# relay_block2.net
KiCad netlist of a schematic drawn in EAGLE
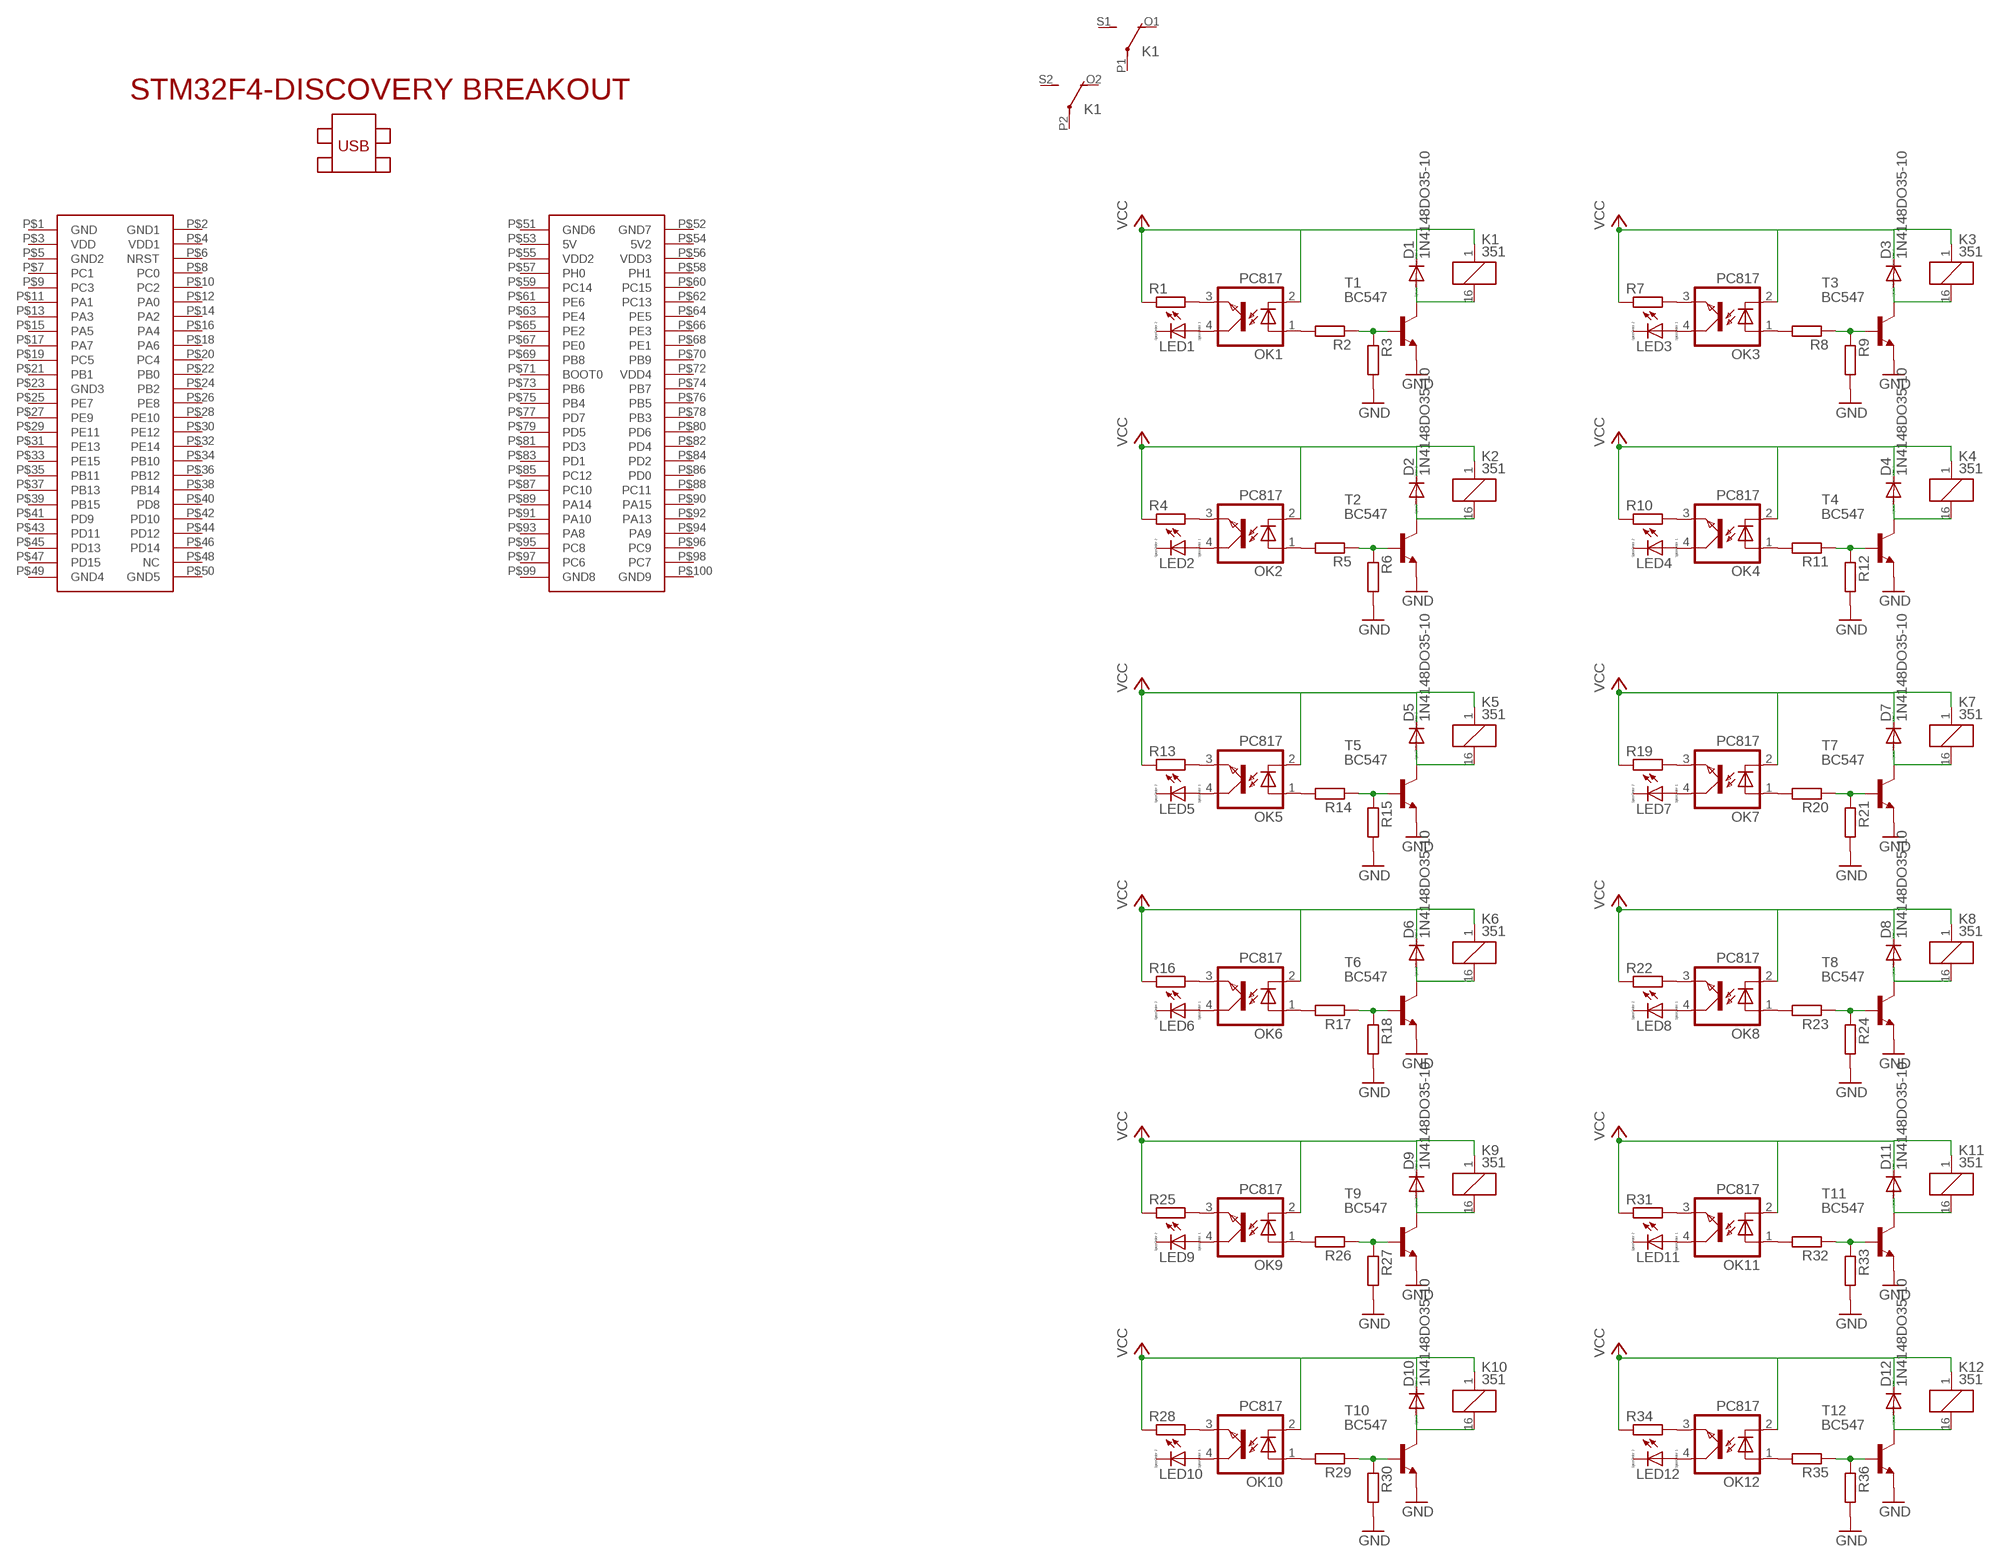
[diagram p0: schematic, sheet 1]

(export (version "E")
  (design (tool "Eeschema 10.0.6"))
  (components
    (comp (ref "D1")
      (value "1N4148DO35-10")
      (footprint "eagle-import:DO35-10")
      (libsource (lib "eagle-import") (part "1N4148DO35-10"))
    )
    (comp (ref "D2")
      (value "1N4148DO35-10")
      (footprint "eagle-import:DO35-10")
      (libsource (lib "eagle-import") (part "1N4148DO35-10"))
    )
    (comp (ref "D3")
      (value "1N4148DO35-10")
      (footprint "eagle-import:DO35-10")
      (libsource (lib "eagle-import") (part "1N4148DO35-10"))
    )
    (comp (ref "D4")
      (value "1N4148DO35-10")
      (footprint "eagle-import:DO35-10")
      (libsource (lib "eagle-import") (part "1N4148DO35-10"))
    )
    (comp (ref "D5")
      (value "1N4148DO35-10")
      (footprint "eagle-import:DO35-10")
      (libsource (lib "eagle-import") (part "1N4148DO35-10"))
    )
    (comp (ref "D6")
      (value "1N4148DO35-10")
      (footprint "eagle-import:DO35-10")
      (libsource (lib "eagle-import") (part "1N4148DO35-10"))
    )
    (comp (ref "D7")
      (value "1N4148DO35-10")
      (footprint "eagle-import:DO35-10")
      (libsource (lib "eagle-import") (part "1N4148DO35-10"))
    )
    (comp (ref "D8")
      (value "1N4148DO35-10")
      (footprint "eagle-import:DO35-10")
      (libsource (lib "eagle-import") (part "1N4148DO35-10"))
    )
    (comp (ref "D9")
      (value "1N4148DO35-10")
      (footprint "eagle-import:DO35-10")
      (libsource (lib "eagle-import") (part "1N4148DO35-10"))
    )
    (comp (ref "D10")
      (value "1N4148DO35-10")
      (footprint "eagle-import:DO35-10")
      (libsource (lib "eagle-import") (part "1N4148DO35-10"))
    )
    (comp (ref "D11")
      (value "1N4148DO35-10")
      (footprint "eagle-import:DO35-10")
      (libsource (lib "eagle-import") (part "1N4148DO35-10"))
    )
    (comp (ref "D12")
      (value "1N4148DO35-10")
      (footprint "eagle-import:DO35-10")
      (libsource (lib "eagle-import") (part "1N4148DO35-10"))
    )
    (comp (ref "K1")
      (value "351")
      (footprint "eagle-import:351")
      (libsource (lib "eagle-import") (part "351"))
    )
    (comp (ref "K2")
      (value "351")
      (footprint "eagle-import:351")
      (libsource (lib "eagle-import") (part "351"))
    )
    (comp (ref "K3")
      (value "351")
      (footprint "eagle-import:351")
      (libsource (lib "eagle-import") (part "351"))
    )
    (comp (ref "K4")
      (value "351")
      (footprint "eagle-import:351")
      (libsource (lib "eagle-import") (part "351"))
    )
    (comp (ref "K5")
      (value "351")
      (footprint "eagle-import:351")
      (libsource (lib "eagle-import") (part "351"))
    )
    (comp (ref "K6")
      (value "351")
      (footprint "eagle-import:351")
      (libsource (lib "eagle-import") (part "351"))
    )
    (comp (ref "K7")
      (value "351")
      (footprint "eagle-import:351")
      (libsource (lib "eagle-import") (part "351"))
    )
    (comp (ref "K8")
      (value "351")
      (footprint "eagle-import:351")
      (libsource (lib "eagle-import") (part "351"))
    )
    (comp (ref "K9")
      (value "351")
      (footprint "eagle-import:351")
      (libsource (lib "eagle-import") (part "351"))
    )
    (comp (ref "K10")
      (value "351")
      (footprint "eagle-import:351")
      (libsource (lib "eagle-import") (part "351"))
    )
    (comp (ref "K11")
      (value "351")
      (footprint "eagle-import:351")
      (libsource (lib "eagle-import") (part "351"))
    )
    (comp (ref "K12")
      (value "351")
      (footprint "eagle-import:351")
      (libsource (lib "eagle-import") (part "351"))
    )
    (comp (ref "LED1")
      (value "LED_ELD260")
      (footprint "eagle-import:LED_LD260")
      (libsource (lib "eagle-import") (part "LED_ELD260"))
    )
    (comp (ref "LED2")
      (value "LED_ELD260")
      (footprint "eagle-import:LED_LD260")
      (libsource (lib "eagle-import") (part "LED_ELD260"))
    )
    (comp (ref "LED3")
      (value "LED_ELD260")
      (footprint "eagle-import:LED_LD260")
      (libsource (lib "eagle-import") (part "LED_ELD260"))
    )
    (comp (ref "LED4")
      (value "LED_ELD260")
      (footprint "eagle-import:LED_LD260")
      (libsource (lib "eagle-import") (part "LED_ELD260"))
    )
    (comp (ref "LED5")
      (value "LED_ELD260")
      (footprint "eagle-import:LED_LD260")
      (libsource (lib "eagle-import") (part "LED_ELD260"))
    )
    (comp (ref "LED6")
      (value "LED_ELD260")
      (footprint "eagle-import:LED_LD260")
      (libsource (lib "eagle-import") (part "LED_ELD260"))
    )
    (comp (ref "LED7")
      (value "LED_ELD260")
      (footprint "eagle-import:LED_LD260")
      (libsource (lib "eagle-import") (part "LED_ELD260"))
    )
    (comp (ref "LED8")
      (value "LED_ELD260")
      (footprint "eagle-import:LED_LD260")
      (libsource (lib "eagle-import") (part "LED_ELD260"))
    )
    (comp (ref "LED9")
      (value "LED_ELD260")
      (footprint "eagle-import:LED_LD260")
      (libsource (lib "eagle-import") (part "LED_ELD260"))
    )
    (comp (ref "LED10")
      (value "LED_ELD260")
      (footprint "eagle-import:LED_LD260")
      (libsource (lib "eagle-import") (part "LED_ELD260"))
    )
    (comp (ref "LED11")
      (value "LED_ELD260")
      (footprint "eagle-import:LED_LD260")
      (libsource (lib "eagle-import") (part "LED_ELD260"))
    )
    (comp (ref "LED12")
      (value "LED_ELD260")
      (footprint "eagle-import:LED_LD260")
      (libsource (lib "eagle-import") (part "LED_ELD260"))
    )
    (comp (ref "OK1")
      (value "PC817")
      (footprint "eagle-import:DIL04")
      (fields (field (name "MPN") "PC817X4J000F"))
      (libsource (lib "eagle-import") (part "PC817"))
    )
    (comp (ref "OK2")
      (value "PC817")
      (footprint "eagle-import:DIL04")
      (fields (field (name "MPN") "PC817X4J000F"))
      (libsource (lib "eagle-import") (part "PC817"))
    )
    (comp (ref "OK3")
      (value "PC817")
      (footprint "eagle-import:DIL04")
      (fields (field (name "MPN") "PC817X4J000F"))
      (libsource (lib "eagle-import") (part "PC817"))
    )
    (comp (ref "OK4")
      (value "PC817")
      (footprint "eagle-import:DIL04")
      (fields (field (name "MPN") "PC817X4J000F"))
      (libsource (lib "eagle-import") (part "PC817"))
    )
    (comp (ref "OK5")
      (value "PC817")
      (footprint "eagle-import:DIL04")
      (fields (field (name "MPN") "PC817X4J000F"))
      (libsource (lib "eagle-import") (part "PC817"))
    )
    (comp (ref "OK6")
      (value "PC817")
      (footprint "eagle-import:DIL04")
      (fields (field (name "MPN") "PC817X4J000F"))
      (libsource (lib "eagle-import") (part "PC817"))
    )
    (comp (ref "OK7")
      (value "PC817")
      (footprint "eagle-import:DIL04")
      (fields (field (name "MPN") "PC817X4J000F"))
      (libsource (lib "eagle-import") (part "PC817"))
    )
    (comp (ref "OK8")
      (value "PC817")
      (footprint "eagle-import:DIL04")
      (fields (field (name "MPN") "PC817X4J000F"))
      (libsource (lib "eagle-import") (part "PC817"))
    )
    (comp (ref "OK9")
      (value "PC817")
      (footprint "eagle-import:DIL04")
      (fields (field (name "MPN") "PC817X4J000F"))
      (libsource (lib "eagle-import") (part "PC817"))
    )
    (comp (ref "OK10")
      (value "PC817")
      (footprint "eagle-import:DIL04")
      (fields (field (name "MPN") "PC817X4J000F"))
      (libsource (lib "eagle-import") (part "PC817"))
    )
    (comp (ref "OK11")
      (value "PC817")
      (footprint "eagle-import:DIL04")
      (fields (field (name "MPN") "PC817X4J000F"))
      (libsource (lib "eagle-import") (part "PC817"))
    )
    (comp (ref "OK12")
      (value "PC817")
      (footprint "eagle-import:DIL04")
      (fields (field (name "MPN") "PC817X4J000F"))
      (libsource (lib "eagle-import") (part "PC817"))
    )
    (comp (ref "R1")
      (value "R-EU_M1206")
      (footprint "eagle-import:M1206")
      (libsource (lib "eagle-import") (part "R-EU_M1206"))
    )
    (comp (ref "R2")
      (value "R-EU_M1206")
      (footprint "eagle-import:M1206")
      (libsource (lib "eagle-import") (part "R-EU_M1206"))
    )
    (comp (ref "R3")
      (value "R-EU_M1206")
      (footprint "eagle-import:M1206")
      (libsource (lib "eagle-import") (part "R-EU_M1206"))
    )
    (comp (ref "R4")
      (value "R-EU_M1206")
      (footprint "eagle-import:M1206")
      (libsource (lib "eagle-import") (part "R-EU_M1206"))
    )
    (comp (ref "R5")
      (value "R-EU_M1206")
      (footprint "eagle-import:M1206")
      (libsource (lib "eagle-import") (part "R-EU_M1206"))
    )
    (comp (ref "R6")
      (value "R-EU_M1206")
      (footprint "eagle-import:M1206")
      (libsource (lib "eagle-import") (part "R-EU_M1206"))
    )
    (comp (ref "R7")
      (value "R-EU_M1206")
      (footprint "eagle-import:M1206")
      (libsource (lib "eagle-import") (part "R-EU_M1206"))
    )
    (comp (ref "R8")
      (value "R-EU_M1206")
      (footprint "eagle-import:M1206")
      (libsource (lib "eagle-import") (part "R-EU_M1206"))
    )
    (comp (ref "R9")
      (value "R-EU_M1206")
      (footprint "eagle-import:M1206")
      (libsource (lib "eagle-import") (part "R-EU_M1206"))
    )
    (comp (ref "R10")
      (value "R-EU_M1206")
      (footprint "eagle-import:M1206")
      (libsource (lib "eagle-import") (part "R-EU_M1206"))
    )
    (comp (ref "R11")
      (value "R-EU_M1206")
      (footprint "eagle-import:M1206")
      (libsource (lib "eagle-import") (part "R-EU_M1206"))
    )
    (comp (ref "R12")
      (value "R-EU_M1206")
      (footprint "eagle-import:M1206")
      (libsource (lib "eagle-import") (part "R-EU_M1206"))
    )
    (comp (ref "R13")
      (value "R-EU_M1206")
      (footprint "eagle-import:M1206")
      (libsource (lib "eagle-import") (part "R-EU_M1206"))
    )
    (comp (ref "R14")
      (value "R-EU_M1206")
      (footprint "eagle-import:M1206")
      (libsource (lib "eagle-import") (part "R-EU_M1206"))
    )
    (comp (ref "R15")
      (value "R-EU_M1206")
      (footprint "eagle-import:M1206")
      (libsource (lib "eagle-import") (part "R-EU_M1206"))
    )
    (comp (ref "R16")
      (value "R-EU_M1206")
      (footprint "eagle-import:M1206")
      (libsource (lib "eagle-import") (part "R-EU_M1206"))
    )
    (comp (ref "R17")
      (value "R-EU_M1206")
      (footprint "eagle-import:M1206")
      (libsource (lib "eagle-import") (part "R-EU_M1206"))
    )
    (comp (ref "R18")
      (value "R-EU_M1206")
      (footprint "eagle-import:M1206")
      (libsource (lib "eagle-import") (part "R-EU_M1206"))
    )
    (comp (ref "R19")
      (value "R-EU_M1206")
      (footprint "eagle-import:M1206")
      (libsource (lib "eagle-import") (part "R-EU_M1206"))
    )
    (comp (ref "R20")
      (value "R-EU_M1206")
      (footprint "eagle-import:M1206")
      (libsource (lib "eagle-import") (part "R-EU_M1206"))
    )
    (comp (ref "R21")
      (value "R-EU_M1206")
      (footprint "eagle-import:M1206")
      (libsource (lib "eagle-import") (part "R-EU_M1206"))
    )
    (comp (ref "R22")
      (value "R-EU_M1206")
      (footprint "eagle-import:M1206")
      (libsource (lib "eagle-import") (part "R-EU_M1206"))
    )
    (comp (ref "R23")
      (value "R-EU_M1206")
      (footprint "eagle-import:M1206")
      (libsource (lib "eagle-import") (part "R-EU_M1206"))
    )
    (comp (ref "R24")
      (value "R-EU_M1206")
      (footprint "eagle-import:M1206")
      (libsource (lib "eagle-import") (part "R-EU_M1206"))
    )
    (comp (ref "R25")
      (value "R-EU_M1206")
      (footprint "eagle-import:M1206")
      (libsource (lib "eagle-import") (part "R-EU_M1206"))
    )
    (comp (ref "R26")
      (value "R-EU_M1206")
      (footprint "eagle-import:M1206")
      (libsource (lib "eagle-import") (part "R-EU_M1206"))
    )
    (comp (ref "R27")
      (value "R-EU_M1206")
      (footprint "eagle-import:M1206")
      (libsource (lib "eagle-import") (part "R-EU_M1206"))
    )
    (comp (ref "R28")
      (value "R-EU_M1206")
      (footprint "eagle-import:M1206")
      (libsource (lib "eagle-import") (part "R-EU_M1206"))
    )
    (comp (ref "R29")
      (value "R-EU_M1206")
      (footprint "eagle-import:M1206")
      (libsource (lib "eagle-import") (part "R-EU_M1206"))
    )
    (comp (ref "R30")
      (value "R-EU_M1206")
      (footprint "eagle-import:M1206")
      (libsource (lib "eagle-import") (part "R-EU_M1206"))
    )
    (comp (ref "R31")
      (value "R-EU_M1206")
      (footprint "eagle-import:M1206")
      (libsource (lib "eagle-import") (part "R-EU_M1206"))
    )
    (comp (ref "R32")
      (value "R-EU_M1206")
      (footprint "eagle-import:M1206")
      (libsource (lib "eagle-import") (part "R-EU_M1206"))
    )
    (comp (ref "R33")
      (value "R-EU_M1206")
      (footprint "eagle-import:M1206")
      (libsource (lib "eagle-import") (part "R-EU_M1206"))
    )
    (comp (ref "R34")
      (value "R-EU_M1206")
      (footprint "eagle-import:M1206")
      (libsource (lib "eagle-import") (part "R-EU_M1206"))
    )
    (comp (ref "R35")
      (value "R-EU_M1206")
      (footprint "eagle-import:M1206")
      (libsource (lib "eagle-import") (part "R-EU_M1206"))
    )
    (comp (ref "R36")
      (value "R-EU_M1206")
      (footprint "eagle-import:M1206")
      (libsource (lib "eagle-import") (part "R-EU_M1206"))
    )
    (comp (ref "T1")
      (value "BC547")
      (footprint "eagle-import:TO92")
      (libsource (lib "eagle-import") (part "BC547"))
    )
    (comp (ref "T2")
      (value "BC547")
      (footprint "eagle-import:TO92")
      (libsource (lib "eagle-import") (part "BC547"))
    )
    (comp (ref "T3")
      (value "BC547")
      (footprint "eagle-import:TO92")
      (libsource (lib "eagle-import") (part "BC547"))
    )
    (comp (ref "T4")
      (value "BC547")
      (footprint "eagle-import:TO92")
      (libsource (lib "eagle-import") (part "BC547"))
    )
    (comp (ref "T5")
      (value "BC547")
      (footprint "eagle-import:TO92")
      (libsource (lib "eagle-import") (part "BC547"))
    )
    (comp (ref "T6")
      (value "BC547")
      (footprint "eagle-import:TO92")
      (libsource (lib "eagle-import") (part "BC547"))
    )
    (comp (ref "T7")
      (value "BC547")
      (footprint "eagle-import:TO92")
      (libsource (lib "eagle-import") (part "BC547"))
    )
    (comp (ref "T8")
      (value "BC547")
      (footprint "eagle-import:TO92")
      (libsource (lib "eagle-import") (part "BC547"))
    )
    (comp (ref "T9")
      (value "BC547")
      (footprint "eagle-import:TO92")
      (libsource (lib "eagle-import") (part "BC547"))
    )
    (comp (ref "T10")
      (value "BC547")
      (footprint "eagle-import:TO92")
      (libsource (lib "eagle-import") (part "BC547"))
    )
    (comp (ref "T11")
      (value "BC547")
      (footprint "eagle-import:TO92")
      (libsource (lib "eagle-import") (part "BC547"))
    )
    (comp (ref "T12")
      (value "BC547")
      (footprint "eagle-import:TO92")
      (libsource (lib "eagle-import") (part "BC547"))
    )
    (comp (ref "U$1")
      (value "STM32F4-DISCOVERY_STM32F4-DISCOVERY")
      (footprint "eagle-import:STM32F4-DISCOVERY_STM32F4-DISCOVERY")
      (libsource (lib "eagle-import") (part "STM32F4-DISCOVERY_STM32F4-DISCOVERY"))
    )
  )
  (nets
    (net (code "1") (name "GND") (class "Default")
      (node (ref "R12") (pin "2") (pinfunction "2_2") (pintype "passive"))
      (node (ref "R15") (pin "2") (pinfunction "2_2") (pintype "passive"))
      (node (ref "R18") (pin "2") (pinfunction "2_2") (pintype "passive"))
      (node (ref "R21") (pin "2") (pinfunction "2_2") (pintype "passive"))
      (node (ref "R24") (pin "2") (pinfunction "2_2") (pintype "passive"))
      (node (ref "R27") (pin "2") (pinfunction "2_2") (pintype "passive"))
      (node (ref "R3") (pin "2") (pinfunction "2_2") (pintype "passive"))
      (node (ref "R30") (pin "2") (pinfunction "2_2") (pintype "passive"))
      (node (ref "R33") (pin "2") (pinfunction "2_2") (pintype "passive"))
      (node (ref "R36") (pin "2") (pinfunction "2_2") (pintype "passive"))
      (node (ref "R6") (pin "2") (pinfunction "2_2") (pintype "passive"))
      (node (ref "R9") (pin "2") (pinfunction "2_2") (pintype "passive"))
      (node (ref "T1") (pin "1") (pinfunction "E_1") (pintype "passive"))
      (node (ref "T10") (pin "1") (pinfunction "E_1") (pintype "passive"))
      (node (ref "T11") (pin "1") (pinfunction "E_1") (pintype "passive"))
      (node (ref "T12") (pin "1") (pinfunction "E_1") (pintype "passive"))
      (node (ref "T2") (pin "1") (pinfunction "E_1") (pintype "passive"))
      (node (ref "T3") (pin "1") (pinfunction "E_1") (pintype "passive"))
      (node (ref "T4") (pin "1") (pinfunction "E_1") (pintype "passive"))
      (node (ref "T5") (pin "1") (pinfunction "E_1") (pintype "passive"))
      (node (ref "T6") (pin "1") (pinfunction "E_1") (pintype "passive"))
      (node (ref "T7") (pin "1") (pinfunction "E_1") (pintype "passive"))
      (node (ref "T8") (pin "1") (pinfunction "E_1") (pintype "passive"))
      (node (ref "T9") (pin "1") (pinfunction "E_1") (pintype "passive"))
    )
    (net (code "2") (name "Net-(K1A-2)") (class "Default")
      (node (ref "D1") (pin "A") (pinfunction "A_A") (pintype "passive"))
      (node (ref "K1") (pin "16") (pinfunction "2_16") (pintype "passive"))
      (node (ref "T1") (pin "3") (pinfunction "C_3") (pintype "passive"))
    )
    (net (code "3") (name "Net-(K2A-2)") (class "Default")
      (node (ref "D2") (pin "A") (pinfunction "A_A") (pintype "passive"))
      (node (ref "K2") (pin "16") (pinfunction "2_16") (pintype "passive"))
      (node (ref "T2") (pin "3") (pinfunction "C_3") (pintype "passive"))
    )
    (net (code "4") (name "Net-(K3A-2)") (class "Default")
      (node (ref "D3") (pin "A") (pinfunction "A_A") (pintype "passive"))
      (node (ref "K3") (pin "16") (pinfunction "2_16") (pintype "passive"))
      (node (ref "T3") (pin "3") (pinfunction "C_3") (pintype "passive"))
    )
    (net (code "5") (name "Net-(K4A-2)") (class "Default")
      (node (ref "D4") (pin "A") (pinfunction "A_A") (pintype "passive"))
      (node (ref "K4") (pin "16") (pinfunction "2_16") (pintype "passive"))
      (node (ref "T4") (pin "3") (pinfunction "C_3") (pintype "passive"))
    )
    (net (code "6") (name "Net-(K5A-2)") (class "Default")
      (node (ref "D5") (pin "A") (pinfunction "A_A") (pintype "passive"))
      (node (ref "K5") (pin "16") (pinfunction "2_16") (pintype "passive"))
      (node (ref "T5") (pin "3") (pinfunction "C_3") (pintype "passive"))
    )
    (net (code "7") (name "Net-(K6A-2)") (class "Default")
      (node (ref "D6") (pin "A") (pinfunction "A_A") (pintype "passive"))
      (node (ref "K6") (pin "16") (pinfunction "2_16") (pintype "passive"))
      (node (ref "T6") (pin "3") (pinfunction "C_3") (pintype "passive"))
    )
    (net (code "8") (name "Net-(K7A-2)") (class "Default")
      (node (ref "D7") (pin "A") (pinfunction "A_A") (pintype "passive"))
      (node (ref "K7") (pin "16") (pinfunction "2_16") (pintype "passive"))
      (node (ref "T7") (pin "3") (pinfunction "C_3") (pintype "passive"))
    )
    (net (code "9") (name "Net-(K8A-2)") (class "Default")
      (node (ref "D8") (pin "A") (pinfunction "A_A") (pintype "passive"))
      (node (ref "K8") (pin "16") (pinfunction "2_16") (pintype "passive"))
      (node (ref "T8") (pin "3") (pinfunction "C_3") (pintype "passive"))
    )
    (net (code "10") (name "Net-(K9A-2)") (class "Default")
      (node (ref "D9") (pin "A") (pinfunction "A_A") (pintype "passive"))
      (node (ref "K9") (pin "16") (pinfunction "2_16") (pintype "passive"))
      (node (ref "T9") (pin "3") (pinfunction "C_3") (pintype "passive"))
    )
    (net (code "11") (name "Net-(K10A-2)") (class "Default")
      (node (ref "D10") (pin "A") (pinfunction "A_A") (pintype "passive"))
      (node (ref "K10") (pin "16") (pinfunction "2_16") (pintype "passive"))
      (node (ref "T10") (pin "3") (pinfunction "C_3") (pintype "passive"))
    )
    (net (code "12") (name "Net-(K11A-2)") (class "Default")
      (node (ref "D11") (pin "A") (pinfunction "A_A") (pintype "passive"))
      (node (ref "K11") (pin "16") (pinfunction "2_16") (pintype "passive"))
      (node (ref "T11") (pin "3") (pinfunction "C_3") (pintype "passive"))
    )
    (net (code "13") (name "Net-(K12A-2)") (class "Default")
      (node (ref "D12") (pin "A") (pinfunction "A_A") (pintype "passive"))
      (node (ref "K12") (pin "16") (pinfunction "2_16") (pintype "passive"))
      (node (ref "T12") (pin "3") (pinfunction "C_3") (pintype "passive"))
    )
    (net (code "14") (name "Net-(OK1-A)") (class "Default")
      (node (ref "OK1") (pin "1") (pinfunction "A_1") (pintype "passive"))
      (node (ref "R2") (pin "2") (pinfunction "2_2") (pintype "passive"))
    )
    (net (code "15") (name "Net-(OK1-COL)") (class "Default")
      (node (ref "LED1") (pin "A") (pinfunction "A_A") (pintype "passive"))
      (node (ref "OK1") (pin "4") (pinfunction "COL_4") (pintype "passive"))
    )
    (net (code "16") (name "Net-(OK1-EMIT)") (class "Default")
      (node (ref "OK1") (pin "3") (pinfunction "EMIT_3") (pintype "passive"))
      (node (ref "R1") (pin "2") (pinfunction "2_2") (pintype "passive"))
    )
    (net (code "17") (name "Net-(OK2-A)") (class "Default")
      (node (ref "OK2") (pin "1") (pinfunction "A_1") (pintype "passive"))
      (node (ref "R5") (pin "2") (pinfunction "2_2") (pintype "passive"))
    )
    (net (code "18") (name "Net-(OK2-COL)") (class "Default")
      (node (ref "LED2") (pin "A") (pinfunction "A_A") (pintype "passive"))
      (node (ref "OK2") (pin "4") (pinfunction "COL_4") (pintype "passive"))
    )
    (net (code "19") (name "Net-(OK2-EMIT)") (class "Default")
      (node (ref "OK2") (pin "3") (pinfunction "EMIT_3") (pintype "passive"))
      (node (ref "R4") (pin "2") (pinfunction "2_2") (pintype "passive"))
    )
    (net (code "20") (name "Net-(OK3-A)") (class "Default")
      (node (ref "OK3") (pin "1") (pinfunction "A_1") (pintype "passive"))
      (node (ref "R8") (pin "2") (pinfunction "2_2") (pintype "passive"))
    )
    (net (code "21") (name "Net-(OK3-COL)") (class "Default")
      (node (ref "LED3") (pin "A") (pinfunction "A_A") (pintype "passive"))
      (node (ref "OK3") (pin "4") (pinfunction "COL_4") (pintype "passive"))
    )
    (net (code "22") (name "Net-(OK3-EMIT)") (class "Default")
      (node (ref "OK3") (pin "3") (pinfunction "EMIT_3") (pintype "passive"))
      (node (ref "R7") (pin "2") (pinfunction "2_2") (pintype "passive"))
    )
    (net (code "23") (name "Net-(OK4-A)") (class "Default")
      (node (ref "OK4") (pin "1") (pinfunction "A_1") (pintype "passive"))
      (node (ref "R11") (pin "2") (pinfunction "2_2") (pintype "passive"))
    )
    (net (code "24") (name "Net-(OK4-COL)") (class "Default")
      (node (ref "LED4") (pin "A") (pinfunction "A_A") (pintype "passive"))
      (node (ref "OK4") (pin "4") (pinfunction "COL_4") (pintype "passive"))
    )
    (net (code "25") (name "Net-(OK4-EMIT)") (class "Default")
      (node (ref "OK4") (pin "3") (pinfunction "EMIT_3") (pintype "passive"))
      (node (ref "R10") (pin "2") (pinfunction "2_2") (pintype "passive"))
    )
    (net (code "26") (name "Net-(OK5-A)") (class "Default")
      (node (ref "OK5") (pin "1") (pinfunction "A_1") (pintype "passive"))
      (node (ref "R14") (pin "2") (pinfunction "2_2") (pintype "passive"))
    )
    (net (code "27") (name "Net-(OK5-COL)") (class "Default")
      (node (ref "LED5") (pin "A") (pinfunction "A_A") (pintype "passive"))
      (node (ref "OK5") (pin "4") (pinfunction "COL_4") (pintype "passive"))
    )
    (net (code "28") (name "Net-(OK5-EMIT)") (class "Default")
      (node (ref "OK5") (pin "3") (pinfunction "EMIT_3") (pintype "passive"))
      (node (ref "R13") (pin "2") (pinfunction "2_2") (pintype "passive"))
    )
    (net (code "29") (name "Net-(OK6-A)") (class "Default")
      (node (ref "OK6") (pin "1") (pinfunction "A_1") (pintype "passive"))
      (node (ref "R17") (pin "2") (pinfunction "2_2") (pintype "passive"))
    )
    (net (code "30") (name "Net-(OK6-COL)") (class "Default")
      (node (ref "LED6") (pin "A") (pinfunction "A_A") (pintype "passive"))
      (node (ref "OK6") (pin "4") (pinfunction "COL_4") (pintype "passive"))
    )
    (net (code "31") (name "Net-(OK6-EMIT)") (class "Default")
      (node (ref "OK6") (pin "3") (pinfunction "EMIT_3") (pintype "passive"))
      (node (ref "R16") (pin "2") (pinfunction "2_2") (pintype "passive"))
    )
    (net (code "32") (name "Net-(OK7-A)") (class "Default")
      (node (ref "OK7") (pin "1") (pinfunction "A_1") (pintype "passive"))
      (node (ref "R20") (pin "2") (pinfunction "2_2") (pintype "passive"))
    )
    (net (code "33") (name "Net-(OK7-COL)") (class "Default")
      (node (ref "LED7") (pin "A") (pinfunction "A_A") (pintype "passive"))
      (node (ref "OK7") (pin "4") (pinfunction "COL_4") (pintype "passive"))
    )
    (net (code "34") (name "Net-(OK7-EMIT)") (class "Default")
      (node (ref "OK7") (pin "3") (pinfunction "EMIT_3") (pintype "passive"))
      (node (ref "R19") (pin "2") (pinfunction "2_2") (pintype "passive"))
    )
    (net (code "35") (name "Net-(OK8-A)") (class "Default")
      (node (ref "OK8") (pin "1") (pinfunction "A_1") (pintype "passive"))
      (node (ref "R23") (pin "2") (pinfunction "2_2") (pintype "passive"))
    )
    (net (code "36") (name "Net-(OK8-COL)") (class "Default")
      (node (ref "LED8") (pin "A") (pinfunction "A_A") (pintype "passive"))
      (node (ref "OK8") (pin "4") (pinfunction "COL_4") (pintype "passive"))
    )
    (net (code "37") (name "Net-(OK8-EMIT)") (class "Default")
      (node (ref "OK8") (pin "3") (pinfunction "EMIT_3") (pintype "passive"))
      (node (ref "R22") (pin "2") (pinfunction "2_2") (pintype "passive"))
    )
    (net (code "38") (name "Net-(OK9-A)") (class "Default")
      (node (ref "OK9") (pin "1") (pinfunction "A_1") (pintype "passive"))
      (node (ref "R26") (pin "2") (pinfunction "2_2") (pintype "passive"))
    )
    (net (code "39") (name "Net-(OK9-COL)") (class "Default")
      (node (ref "LED9") (pin "A") (pinfunction "A_A") (pintype "passive"))
      (node (ref "OK9") (pin "4") (pinfunction "COL_4") (pintype "passive"))
    )
    (net (code "40") (name "Net-(OK9-EMIT)") (class "Default")
      (node (ref "OK9") (pin "3") (pinfunction "EMIT_3") (pintype "passive"))
      (node (ref "R25") (pin "2") (pinfunction "2_2") (pintype "passive"))
    )
    (net (code "41") (name "Net-(OK10-A)") (class "Default")
      (node (ref "OK10") (pin "1") (pinfunction "A_1") (pintype "passive"))
      (node (ref "R29") (pin "2") (pinfunction "2_2") (pintype "passive"))
    )
    (net (code "42") (name "Net-(OK10-COL)") (class "Default")
      (node (ref "LED10") (pin "A") (pinfunction "A_A") (pintype "passive"))
      (node (ref "OK10") (pin "4") (pinfunction "COL_4") (pintype "passive"))
    )
    (net (code "43") (name "Net-(OK10-EMIT)") (class "Default")
      (node (ref "OK10") (pin "3") (pinfunction "EMIT_3") (pintype "passive"))
      (node (ref "R28") (pin "2") (pinfunction "2_2") (pintype "passive"))
    )
    (net (code "44") (name "Net-(OK11-A)") (class "Default")
      (node (ref "OK11") (pin "1") (pinfunction "A_1") (pintype "passive"))
      (node (ref "R32") (pin "2") (pinfunction "2_2") (pintype "passive"))
    )
    (net (code "45") (name "Net-(OK11-COL)") (class "Default")
      (node (ref "LED11") (pin "A") (pinfunction "A_A") (pintype "passive"))
      (node (ref "OK11") (pin "4") (pinfunction "COL_4") (pintype "passive"))
    )
    (net (code "46") (name "Net-(OK11-EMIT)") (class "Default")
      (node (ref "OK11") (pin "3") (pinfunction "EMIT_3") (pintype "passive"))
      (node (ref "R31") (pin "2") (pinfunction "2_2") (pintype "passive"))
    )
    (net (code "47") (name "Net-(OK12-A)") (class "Default")
      (node (ref "OK12") (pin "1") (pinfunction "A_1") (pintype "passive"))
      (node (ref "R35") (pin "2") (pinfunction "2_2") (pintype "passive"))
    )
    (net (code "48") (name "Net-(OK12-COL)") (class "Default")
      (node (ref "LED12") (pin "A") (pinfunction "A_A") (pintype "passive"))
      (node (ref "OK12") (pin "4") (pinfunction "COL_4") (pintype "passive"))
    )
    (net (code "49") (name "Net-(OK12-EMIT)") (class "Default")
      (node (ref "OK12") (pin "3") (pinfunction "EMIT_3") (pintype "passive"))
      (node (ref "R34") (pin "2") (pinfunction "2_2") (pintype "passive"))
    )
    (net (code "50") (name "Net-(T1-B)") (class "Default")
      (node (ref "R2") (pin "1") (pinfunction "1_1") (pintype "passive"))
      (node (ref "R3") (pin "1") (pinfunction "1_1") (pintype "passive"))
      (node (ref "T1") (pin "2") (pinfunction "B_2") (pintype "passive"))
    )
    (net (code "51") (name "Net-(T2-B)") (class "Default")
      (node (ref "R5") (pin "1") (pinfunction "1_1") (pintype "passive"))
      (node (ref "R6") (pin "1") (pinfunction "1_1") (pintype "passive"))
      (node (ref "T2") (pin "2") (pinfunction "B_2") (pintype "passive"))
    )
    (net (code "52") (name "Net-(T3-B)") (class "Default")
      (node (ref "R8") (pin "1") (pinfunction "1_1") (pintype "passive"))
      (node (ref "R9") (pin "1") (pinfunction "1_1") (pintype "passive"))
      (node (ref "T3") (pin "2") (pinfunction "B_2") (pintype "passive"))
    )
    (net (code "53") (name "Net-(T4-B)") (class "Default")
      (node (ref "R11") (pin "1") (pinfunction "1_1") (pintype "passive"))
      (node (ref "R12") (pin "1") (pinfunction "1_1") (pintype "passive"))
      (node (ref "T4") (pin "2") (pinfunction "B_2") (pintype "passive"))
    )
    (net (code "54") (name "Net-(T5-B)") (class "Default")
      (node (ref "R14") (pin "1") (pinfunction "1_1") (pintype "passive"))
      (node (ref "R15") (pin "1") (pinfunction "1_1") (pintype "passive"))
      (node (ref "T5") (pin "2") (pinfunction "B_2") (pintype "passive"))
    )
    (net (code "55") (name "Net-(T6-B)") (class "Default")
      (node (ref "R17") (pin "1") (pinfunction "1_1") (pintype "passive"))
      (node (ref "R18") (pin "1") (pinfunction "1_1") (pintype "passive"))
      (node (ref "T6") (pin "2") (pinfunction "B_2") (pintype "passive"))
    )
    (net (code "56") (name "Net-(T7-B)") (class "Default")
      (node (ref "R20") (pin "1") (pinfunction "1_1") (pintype "passive"))
      (node (ref "R21") (pin "1") (pinfunction "1_1") (pintype "passive"))
      (node (ref "T7") (pin "2") (pinfunction "B_2") (pintype "passive"))
    )
    (net (code "57") (name "Net-(T8-B)") (class "Default")
      (node (ref "R23") (pin "1") (pinfunction "1_1") (pintype "passive"))
      (node (ref "R24") (pin "1") (pinfunction "1_1") (pintype "passive"))
      (node (ref "T8") (pin "2") (pinfunction "B_2") (pintype "passive"))
    )
    (net (code "58") (name "Net-(T9-B)") (class "Default")
      (node (ref "R26") (pin "1") (pinfunction "1_1") (pintype "passive"))
      (node (ref "R27") (pin "1") (pinfunction "1_1") (pintype "passive"))
      (node (ref "T9") (pin "2") (pinfunction "B_2") (pintype "passive"))
    )
    (net (code "59") (name "Net-(T10-B)") (class "Default")
      (node (ref "R29") (pin "1") (pinfunction "1_1") (pintype "passive"))
      (node (ref "R30") (pin "1") (pinfunction "1_1") (pintype "passive"))
      (node (ref "T10") (pin "2") (pinfunction "B_2") (pintype "passive"))
    )
    (net (code "60") (name "Net-(T11-B)") (class "Default")
      (node (ref "R32") (pin "1") (pinfunction "1_1") (pintype "passive"))
      (node (ref "R33") (pin "1") (pinfunction "1_1") (pintype "passive"))
      (node (ref "T11") (pin "2") (pinfunction "B_2") (pintype "passive"))
    )
    (net (code "61") (name "Net-(T12-B)") (class "Default")
      (node (ref "R35") (pin "1") (pinfunction "1_1") (pintype "passive"))
      (node (ref "R36") (pin "1") (pinfunction "1_1") (pintype "passive"))
      (node (ref "T12") (pin "2") (pinfunction "B_2") (pintype "passive"))
    )
    (net (code "62") (name "VCC") (class "Default")
      (node (ref "D1") (pin "C") (pinfunction "C_C") (pintype "passive"))
      (node (ref "D10") (pin "C") (pinfunction "C_C") (pintype "passive"))
      (node (ref "D11") (pin "C") (pinfunction "C_C") (pintype "passive"))
      (node (ref "D12") (pin "C") (pinfunction "C_C") (pintype "passive"))
      (node (ref "D2") (pin "C") (pinfunction "C_C") (pintype "passive"))
      (node (ref "D3") (pin "C") (pinfunction "C_C") (pintype "passive"))
      (node (ref "D4") (pin "C") (pinfunction "C_C") (pintype "passive"))
      (node (ref "D5") (pin "C") (pinfunction "C_C") (pintype "passive"))
      (node (ref "D6") (pin "C") (pinfunction "C_C") (pintype "passive"))
      (node (ref "D7") (pin "C") (pinfunction "C_C") (pintype "passive"))
      (node (ref "D8") (pin "C") (pinfunction "C_C") (pintype "passive"))
      (node (ref "D9") (pin "C") (pinfunction "C_C") (pintype "passive"))
      (node (ref "K1") (pin "1") (pinfunction "1_1") (pintype "passive"))
      (node (ref "K10") (pin "1") (pinfunction "1_1") (pintype "passive"))
      (node (ref "K11") (pin "1") (pinfunction "1_1") (pintype "passive"))
      (node (ref "K12") (pin "1") (pinfunction "1_1") (pintype "passive"))
      (node (ref "K2") (pin "1") (pinfunction "1_1") (pintype "passive"))
      (node (ref "K3") (pin "1") (pinfunction "1_1") (pintype "passive"))
      (node (ref "K4") (pin "1") (pinfunction "1_1") (pintype "passive"))
      (node (ref "K5") (pin "1") (pinfunction "1_1") (pintype "passive"))
      (node (ref "K6") (pin "1") (pinfunction "1_1") (pintype "passive"))
      (node (ref "K7") (pin "1") (pinfunction "1_1") (pintype "passive"))
      (node (ref "K8") (pin "1") (pinfunction "1_1") (pintype "passive"))
      (node (ref "K9") (pin "1") (pinfunction "1_1") (pintype "passive"))
      (node (ref "OK1") (pin "2") (pinfunction "C_2") (pintype "passive"))
      (node (ref "OK10") (pin "2") (pinfunction "C_2") (pintype "passive"))
      (node (ref "OK11") (pin "2") (pinfunction "C_2") (pintype "passive"))
      (node (ref "OK12") (pin "2") (pinfunction "C_2") (pintype "passive"))
      (node (ref "OK2") (pin "2") (pinfunction "C_2") (pintype "passive"))
      (node (ref "OK3") (pin "2") (pinfunction "C_2") (pintype "passive"))
      (node (ref "OK4") (pin "2") (pinfunction "C_2") (pintype "passive"))
      (node (ref "OK5") (pin "2") (pinfunction "C_2") (pintype "passive"))
      (node (ref "OK6") (pin "2") (pinfunction "C_2") (pintype "passive"))
      (node (ref "OK7") (pin "2") (pinfunction "C_2") (pintype "passive"))
      (node (ref "OK8") (pin "2") (pinfunction "C_2") (pintype "passive"))
      (node (ref "OK9") (pin "2") (pinfunction "C_2") (pintype "passive"))
      (node (ref "R1") (pin "1") (pinfunction "1_1") (pintype "passive"))
      (node (ref "R10") (pin "1") (pinfunction "1_1") (pintype "passive"))
      (node (ref "R13") (pin "1") (pinfunction "1_1") (pintype "passive"))
      (node (ref "R16") (pin "1") (pinfunction "1_1") (pintype "passive"))
      (node (ref "R19") (pin "1") (pinfunction "1_1") (pintype "passive"))
      (node (ref "R22") (pin "1") (pinfunction "1_1") (pintype "passive"))
      (node (ref "R25") (pin "1") (pinfunction "1_1") (pintype "passive"))
      (node (ref "R28") (pin "1") (pinfunction "1_1") (pintype "passive"))
      (node (ref "R31") (pin "1") (pinfunction "1_1") (pintype "passive"))
      (node (ref "R34") (pin "1") (pinfunction "1_1") (pintype "passive"))
      (node (ref "R4") (pin "1") (pinfunction "1_1") (pintype "passive"))
      (node (ref "R7") (pin "1") (pinfunction "1_1") (pintype "passive"))
    )
    (net (code "63") (name "unconnected-(K1B-O-PadO1)") (class "Default")
      (node (ref "K1") (pin "O1") (pinfunction "O_O1") (pintype "passive"))
    )
    (net (code "64") (name "unconnected-(K1B-P-PadP1)") (class "Default")
      (node (ref "K1") (pin "P1") (pinfunction "P_P1") (pintype "passive"))
    )
    (net (code "65") (name "unconnected-(K1B-S-PadS1)") (class "Default")
      (node (ref "K1") (pin "S1") (pinfunction "S_S1") (pintype "passive"))
    )
    (net (code "66") (name "unconnected-(K1C-O-PadO2)") (class "Default")
      (node (ref "K1") (pin "O2") (pinfunction "O_O2") (pintype "passive"))
    )
    (net (code "67") (name "unconnected-(K1C-P-PadP2)") (class "Default")
      (node (ref "K1") (pin "P2") (pinfunction "P_P2") (pintype "passive"))
    )
    (net (code "68") (name "unconnected-(K1C-S-PadS2)") (class "Default")
      (node (ref "K1") (pin "S2") (pinfunction "S_S2") (pintype "passive"))
    )
    (net (code "69") (name "unconnected-(LED1-C-PadK)") (class "Default")
      (node (ref "LED1") (pin "K") (pinfunction "C_K") (pintype "passive"))
    )
    (net (code "70") (name "unconnected-(LED2-C-PadK)") (class "Default")
      (node (ref "LED2") (pin "K") (pinfunction "C_K") (pintype "passive"))
    )
    (net (code "71") (name "unconnected-(LED3-C-PadK)") (class "Default")
      (node (ref "LED3") (pin "K") (pinfunction "C_K") (pintype "passive"))
    )
    (net (code "72") (name "unconnected-(LED4-C-PadK)") (class "Default")
      (node (ref "LED4") (pin "K") (pinfunction "C_K") (pintype "passive"))
    )
    (net (code "73") (name "unconnected-(LED5-C-PadK)") (class "Default")
      (node (ref "LED5") (pin "K") (pinfunction "C_K") (pintype "passive"))
    )
    (net (code "74") (name "unconnected-(LED6-C-PadK)") (class "Default")
      (node (ref "LED6") (pin "K") (pinfunction "C_K") (pintype "passive"))
    )
    (net (code "75") (name "unconnected-(LED7-C-PadK)") (class "Default")
      (node (ref "LED7") (pin "K") (pinfunction "C_K") (pintype "passive"))
    )
    (net (code "76") (name "unconnected-(LED8-C-PadK)") (class "Default")
      (node (ref "LED8") (pin "K") (pinfunction "C_K") (pintype "passive"))
    )
    (net (code "77") (name "unconnected-(LED9-C-PadK)") (class "Default")
      (node (ref "LED9") (pin "K") (pinfunction "C_K") (pintype "passive"))
    )
    (net (code "78") (name "unconnected-(LED10-C-PadK)") (class "Default")
      (node (ref "LED10") (pin "K") (pinfunction "C_K") (pintype "passive"))
    )
    (net (code "79") (name "unconnected-(LED11-C-PadK)") (class "Default")
      (node (ref "LED11") (pin "K") (pinfunction "C_K") (pintype "passive"))
    )
    (net (code "80") (name "unconnected-(LED12-C-PadK)") (class "Default")
      (node (ref "LED12") (pin "K") (pinfunction "C_K") (pintype "passive"))
    )
    (net (code "81") (name "unconnected-(U$1-5V-PadP$53)") (class "Default")
      (node (ref "U$1") (pin "P$53") (pinfunction "5V_P$53") (pintype "bidirectional"))
    )
    (net (code "82") (name "unconnected-(U$1-5V2-PadP$54)") (class "Default")
      (node (ref "U$1") (pin "P$54") (pinfunction "5V2_P$54") (pintype "bidirectional"))
    )
    (net (code "83") (name "unconnected-(U$1-BOOT0-PadP$71)") (class "Default")
      (node (ref "U$1") (pin "P$71") (pinfunction "BOOT0_P$71") (pintype "bidirectional"))
    )
    (net (code "84") (name "unconnected-(U$1-GND-PadP$1)") (class "Default")
      (node (ref "U$1") (pin "P$1") (pinfunction "GND_P$1") (pintype "bidirectional"))
    )
    (net (code "85") (name "unconnected-(U$1-GND1-PadP$2)") (class "Default")
      (node (ref "U$1") (pin "P$2") (pinfunction "GND1_P$2") (pintype "bidirectional"))
    )
    (net (code "86") (name "unconnected-(U$1-GND2-PadP$5)") (class "Default")
      (node (ref "U$1") (pin "P$5") (pinfunction "GND2_P$5") (pintype "bidirectional"))
    )
    (net (code "87") (name "unconnected-(U$1-GND3-PadP$23)") (class "Default")
      (node (ref "U$1") (pin "P$23") (pinfunction "GND3_P$23") (pintype "bidirectional"))
    )
    (net (code "88") (name "unconnected-(U$1-GND4-PadP$49)") (class "Default")
      (node (ref "U$1") (pin "P$49") (pinfunction "GND4_P$49") (pintype "bidirectional"))
    )
    (net (code "89") (name "unconnected-(U$1-GND5-PadP$50)") (class "Default")
      (node (ref "U$1") (pin "P$50") (pinfunction "GND5_P$50") (pintype "bidirectional"))
    )
    (net (code "90") (name "unconnected-(U$1-GND6-PadP$51)") (class "Default")
      (node (ref "U$1") (pin "P$51") (pinfunction "GND6_P$51") (pintype "bidirectional"))
    )
    (net (code "91") (name "unconnected-(U$1-GND7-PadP$52)") (class "Default")
      (node (ref "U$1") (pin "P$52") (pinfunction "GND7_P$52") (pintype "bidirectional"))
    )
    (net (code "92") (name "unconnected-(U$1-GND8-PadP$99)") (class "Default")
      (node (ref "U$1") (pin "P$99") (pinfunction "GND8_P$99") (pintype "bidirectional"))
    )
    (net (code "93") (name "unconnected-(U$1-GND9-PadP$100)") (class "Default")
      (node (ref "U$1") (pin "P$100") (pinfunction "GND9_P$100") (pintype "bidirectional"))
    )
    (net (code "94") (name "unconnected-(U$1-NC-PadP$48)") (class "Default")
      (node (ref "U$1") (pin "P$48") (pinfunction "NC_P$48") (pintype "bidirectional"))
    )
    (net (code "95") (name "unconnected-(U$1-NRST-PadP$6)") (class "Default")
      (node (ref "U$1") (pin "P$6") (pinfunction "NRST_P$6") (pintype "bidirectional"))
    )
    (net (code "96") (name "unconnected-(U$1-PA0-PadP$12)") (class "Default")
      (node (ref "U$1") (pin "P$12") (pinfunction "PA0_P$12") (pintype "bidirectional"))
    )
    (net (code "97") (name "unconnected-(U$1-PA1-PadP$11)") (class "Default")
      (node (ref "U$1") (pin "P$11") (pinfunction "PA1_P$11") (pintype "bidirectional"))
    )
    (net (code "98") (name "unconnected-(U$1-PA2-PadP$14)") (class "Default")
      (node (ref "U$1") (pin "P$14") (pinfunction "PA2_P$14") (pintype "bidirectional"))
    )
    (net (code "99") (name "unconnected-(U$1-PA3-PadP$13)") (class "Default")
      (node (ref "U$1") (pin "P$13") (pinfunction "PA3_P$13") (pintype "bidirectional"))
    )
    (net (code "100") (name "unconnected-(U$1-PA4-PadP$16)") (class "Default")
      (node (ref "U$1") (pin "P$16") (pinfunction "PA4_P$16") (pintype "bidirectional"))
    )
    (net (code "101") (name "unconnected-(U$1-PA5-PadP$15)") (class "Default")
      (node (ref "U$1") (pin "P$15") (pinfunction "PA5_P$15") (pintype "bidirectional"))
    )
    (net (code "102") (name "unconnected-(U$1-PA6-PadP$18)") (class "Default")
      (node (ref "U$1") (pin "P$18") (pinfunction "PA6_P$18") (pintype "bidirectional"))
    )
    (net (code "103") (name "unconnected-(U$1-PA7-PadP$17)") (class "Default")
      (node (ref "U$1") (pin "P$17") (pinfunction "PA7_P$17") (pintype "bidirectional"))
    )
    (net (code "104") (name "unconnected-(U$1-PA8-PadP$93)") (class "Default")
      (node (ref "U$1") (pin "P$93") (pinfunction "PA8_P$93") (pintype "bidirectional"))
    )
    (net (code "105") (name "unconnected-(U$1-PA9-PadP$94)") (class "Default")
      (node (ref "U$1") (pin "P$94") (pinfunction "PA9_P$94") (pintype "bidirectional"))
    )
    (net (code "106") (name "unconnected-(U$1-PA10-PadP$91)") (class "Default")
      (node (ref "U$1") (pin "P$91") (pinfunction "PA10_P$91") (pintype "bidirectional"))
    )
    (net (code "107") (name "unconnected-(U$1-PA13-PadP$92)") (class "Default")
      (node (ref "U$1") (pin "P$92") (pinfunction "PA13_P$92") (pintype "bidirectional"))
    )
    (net (code "108") (name "unconnected-(U$1-PA14-PadP$89)") (class "Default")
      (node (ref "U$1") (pin "P$89") (pinfunction "PA14_P$89") (pintype "bidirectional"))
    )
    (net (code "109") (name "unconnected-(U$1-PA15-PadP$90)") (class "Default")
      (node (ref "U$1") (pin "P$90") (pinfunction "PA15_P$90") (pintype "bidirectional"))
    )
    (net (code "110") (name "unconnected-(U$1-PB0-PadP$22)") (class "Default")
      (node (ref "U$1") (pin "P$22") (pinfunction "PB0_P$22") (pintype "bidirectional"))
    )
    (net (code "111") (name "unconnected-(U$1-PB1-PadP$21)") (class "Default")
      (node (ref "U$1") (pin "P$21") (pinfunction "PB1_P$21") (pintype "bidirectional"))
    )
    (net (code "112") (name "unconnected-(U$1-PB2-PadP$24)") (class "Default")
      (node (ref "U$1") (pin "P$24") (pinfunction "PB2_P$24") (pintype "bidirectional"))
    )
    (net (code "113") (name "unconnected-(U$1-PB3-PadP$78)") (class "Default")
      (node (ref "U$1") (pin "P$78") (pinfunction "PB3_P$78") (pintype "bidirectional"))
    )
    (net (code "114") (name "unconnected-(U$1-PB4-PadP$75)") (class "Default")
      (node (ref "U$1") (pin "P$75") (pinfunction "PB4_P$75") (pintype "bidirectional"))
    )
    (net (code "115") (name "unconnected-(U$1-PB5-PadP$76)") (class "Default")
      (node (ref "U$1") (pin "P$76") (pinfunction "PB5_P$76") (pintype "bidirectional"))
    )
    (net (code "116") (name "unconnected-(U$1-PB6-PadP$73)") (class "Default")
      (node (ref "U$1") (pin "P$73") (pinfunction "PB6_P$73") (pintype "bidirectional"))
    )
    (net (code "117") (name "unconnected-(U$1-PB7-PadP$74)") (class "Default")
      (node (ref "U$1") (pin "P$74") (pinfunction "PB7_P$74") (pintype "bidirectional"))
    )
    (net (code "118") (name "unconnected-(U$1-PB8-PadP$69)") (class "Default")
      (node (ref "U$1") (pin "P$69") (pinfunction "PB8_P$69") (pintype "bidirectional"))
    )
    (net (code "119") (name "unconnected-(U$1-PB9-PadP$70)") (class "Default")
      (node (ref "U$1") (pin "P$70") (pinfunction "PB9_P$70") (pintype "bidirectional"))
    )
    (net (code "120") (name "unconnected-(U$1-PB10-PadP$34)") (class "Default")
      (node (ref "U$1") (pin "P$34") (pinfunction "PB10_P$34") (pintype "bidirectional"))
    )
    (net (code "121") (name "unconnected-(U$1-PB11-PadP$35)") (class "Default")
      (node (ref "U$1") (pin "P$35") (pinfunction "PB11_P$35") (pintype "bidirectional"))
    )
    (net (code "122") (name "unconnected-(U$1-PB12-PadP$36)") (class "Default")
      (node (ref "U$1") (pin "P$36") (pinfunction "PB12_P$36") (pintype "bidirectional"))
    )
    (net (code "123") (name "unconnected-(U$1-PB13-PadP$37)") (class "Default")
      (node (ref "U$1") (pin "P$37") (pinfunction "PB13_P$37") (pintype "bidirectional"))
    )
    (net (code "124") (name "unconnected-(U$1-PB14-PadP$38)") (class "Default")
      (node (ref "U$1") (pin "P$38") (pinfunction "PB14_P$38") (pintype "bidirectional"))
    )
    (net (code "125") (name "unconnected-(U$1-PB15-PadP$39)") (class "Default")
      (node (ref "U$1") (pin "P$39") (pinfunction "PB15_P$39") (pintype "bidirectional"))
    )
    (net (code "126") (name "unconnected-(U$1-PC0-PadP$8)") (class "Default")
      (node (ref "U$1") (pin "P$8") (pinfunction "PC0_P$8") (pintype "bidirectional"))
    )
    (net (code "127") (name "unconnected-(U$1-PC1-PadP$7)") (class "Default")
      (node (ref "U$1") (pin "P$7") (pinfunction "PC1_P$7") (pintype "bidirectional"))
    )
    (net (code "128") (name "unconnected-(U$1-PC2-PadP$10)") (class "Default")
      (node (ref "U$1") (pin "P$10") (pinfunction "PC2_P$10") (pintype "bidirectional"))
    )
    (net (code "129") (name "unconnected-(U$1-PC3-PadP$9)") (class "Default")
      (node (ref "U$1") (pin "P$9") (pinfunction "PC3_P$9") (pintype "bidirectional"))
    )
    (net (code "130") (name "unconnected-(U$1-PC4-PadP$20)") (class "Default")
      (node (ref "U$1") (pin "P$20") (pinfunction "PC4_P$20") (pintype "bidirectional"))
    )
    (net (code "131") (name "unconnected-(U$1-PC5-PadP$19)") (class "Default")
      (node (ref "U$1") (pin "P$19") (pinfunction "PC5_P$19") (pintype "bidirectional"))
    )
    (net (code "132") (name "unconnected-(U$1-PC6-PadP$97)") (class "Default")
      (node (ref "U$1") (pin "P$97") (pinfunction "PC6_P$97") (pintype "bidirectional"))
    )
    (net (code "133") (name "unconnected-(U$1-PC7-PadP$98)") (class "Default")
      (node (ref "U$1") (pin "P$98") (pinfunction "PC7_P$98") (pintype "bidirectional"))
    )
    (net (code "134") (name "unconnected-(U$1-PC8-PadP$95)") (class "Default")
      (node (ref "U$1") (pin "P$95") (pinfunction "PC8_P$95") (pintype "bidirectional"))
    )
    (net (code "135") (name "unconnected-(U$1-PC9-PadP$96)") (class "Default")
      (node (ref "U$1") (pin "P$96") (pinfunction "PC9_P$96") (pintype "bidirectional"))
    )
    (net (code "136") (name "unconnected-(U$1-PC10-PadP$87)") (class "Default")
      (node (ref "U$1") (pin "P$87") (pinfunction "PC10_P$87") (pintype "bidirectional"))
    )
    (net (code "137") (name "unconnected-(U$1-PC11-PadP$88)") (class "Default")
      (node (ref "U$1") (pin "P$88") (pinfunction "PC11_P$88") (pintype "bidirectional"))
    )
    (net (code "138") (name "unconnected-(U$1-PC12-PadP$85)") (class "Default")
      (node (ref "U$1") (pin "P$85") (pinfunction "PC12_P$85") (pintype "bidirectional"))
    )
    (net (code "139") (name "unconnected-(U$1-PC13-PadP$62)") (class "Default")
      (node (ref "U$1") (pin "P$62") (pinfunction "PC13_P$62") (pintype "bidirectional"))
    )
    (net (code "140") (name "unconnected-(U$1-PC14-PadP$59)") (class "Default")
      (node (ref "U$1") (pin "P$59") (pinfunction "PC14_P$59") (pintype "bidirectional"))
    )
    (net (code "141") (name "unconnected-(U$1-PC15-PadP$60)") (class "Default")
      (node (ref "U$1") (pin "P$60") (pinfunction "PC15_P$60") (pintype "bidirectional"))
    )
    (net (code "142") (name "unconnected-(U$1-PD0-PadP$86)") (class "Default")
      (node (ref "U$1") (pin "P$86") (pinfunction "PD0_P$86") (pintype "bidirectional"))
    )
    (net (code "143") (name "unconnected-(U$1-PD1-PadP$83)") (class "Default")
      (node (ref "U$1") (pin "P$83") (pinfunction "PD1_P$83") (pintype "bidirectional"))
    )
    (net (code "144") (name "unconnected-(U$1-PD2-PadP$84)") (class "Default")
      (node (ref "U$1") (pin "P$84") (pinfunction "PD2_P$84") (pintype "bidirectional"))
    )
    (net (code "145") (name "unconnected-(U$1-PD3-PadP$81)") (class "Default")
      (node (ref "U$1") (pin "P$81") (pinfunction "PD3_P$81") (pintype "bidirectional"))
    )
    (net (code "146") (name "unconnected-(U$1-PD4-PadP$82)") (class "Default")
      (node (ref "U$1") (pin "P$82") (pinfunction "PD4_P$82") (pintype "bidirectional"))
    )
    (net (code "147") (name "unconnected-(U$1-PD5-PadP$79)") (class "Default")
      (node (ref "U$1") (pin "P$79") (pinfunction "PD5_P$79") (pintype "bidirectional"))
    )
    (net (code "148") (name "unconnected-(U$1-PD6-PadP$80)") (class "Default")
      (node (ref "U$1") (pin "P$80") (pinfunction "PD6_P$80") (pintype "bidirectional"))
    )
    (net (code "149") (name "unconnected-(U$1-PD7-PadP$77)") (class "Default")
      (node (ref "U$1") (pin "P$77") (pinfunction "PD7_P$77") (pintype "bidirectional"))
    )
    (net (code "150") (name "unconnected-(U$1-PD8-PadP$40)") (class "Default")
      (node (ref "U$1") (pin "P$40") (pinfunction "PD8_P$40") (pintype "bidirectional"))
    )
    (net (code "151") (name "unconnected-(U$1-PD9-PadP$41)") (class "Default")
      (node (ref "U$1") (pin "P$41") (pinfunction "PD9_P$41") (pintype "bidirectional"))
    )
    (net (code "152") (name "unconnected-(U$1-PD10-PadP$42)") (class "Default")
      (node (ref "U$1") (pin "P$42") (pinfunction "PD10_P$42") (pintype "bidirectional"))
    )
    (net (code "153") (name "unconnected-(U$1-PD11-PadP$43)") (class "Default")
      (node (ref "U$1") (pin "P$43") (pinfunction "PD11_P$43") (pintype "bidirectional"))
    )
    (net (code "154") (name "unconnected-(U$1-PD12-PadP$44)") (class "Default")
      (node (ref "U$1") (pin "P$44") (pinfunction "PD12_P$44") (pintype "bidirectional"))
    )
    (net (code "155") (name "unconnected-(U$1-PD13-PadP$45)") (class "Default")
      (node (ref "U$1") (pin "P$45") (pinfunction "PD13_P$45") (pintype "bidirectional"))
    )
    (net (code "156") (name "unconnected-(U$1-PD14-PadP$46)") (class "Default")
      (node (ref "U$1") (pin "P$46") (pinfunction "PD14_P$46") (pintype "bidirectional"))
    )
    (net (code "157") (name "unconnected-(U$1-PD15-PadP$47)") (class "Default")
      (node (ref "U$1") (pin "P$47") (pinfunction "PD15_P$47") (pintype "bidirectional"))
    )
    (net (code "158") (name "unconnected-(U$1-PE0-PadP$67)") (class "Default")
      (node (ref "U$1") (pin "P$67") (pinfunction "PE0_P$67") (pintype "bidirectional"))
    )
    (net (code "159") (name "unconnected-(U$1-PE1-PadP$68)") (class "Default")
      (node (ref "U$1") (pin "P$68") (pinfunction "PE1_P$68") (pintype "bidirectional"))
    )
    (net (code "160") (name "unconnected-(U$1-PE2-PadP$65)") (class "Default")
      (node (ref "U$1") (pin "P$65") (pinfunction "PE2_P$65") (pintype "bidirectional"))
    )
    (net (code "161") (name "unconnected-(U$1-PE3-PadP$66)") (class "Default")
      (node (ref "U$1") (pin "P$66") (pinfunction "PE3_P$66") (pintype "bidirectional"))
    )
    (net (code "162") (name "unconnected-(U$1-PE4-PadP$63)") (class "Default")
      (node (ref "U$1") (pin "P$63") (pinfunction "PE4_P$63") (pintype "bidirectional"))
    )
    (net (code "163") (name "unconnected-(U$1-PE5-PadP$64)") (class "Default")
      (node (ref "U$1") (pin "P$64") (pinfunction "PE5_P$64") (pintype "bidirectional"))
    )
    (net (code "164") (name "unconnected-(U$1-PE6-PadP$61)") (class "Default")
      (node (ref "U$1") (pin "P$61") (pinfunction "PE6_P$61") (pintype "bidirectional"))
    )
    (net (code "165") (name "unconnected-(U$1-PE7-PadP$25)") (class "Default")
      (node (ref "U$1") (pin "P$25") (pinfunction "PE7_P$25") (pintype "bidirectional"))
    )
    (net (code "166") (name "unconnected-(U$1-PE8-PadP$26)") (class "Default")
      (node (ref "U$1") (pin "P$26") (pinfunction "PE8_P$26") (pintype "bidirectional"))
    )
    (net (code "167") (name "unconnected-(U$1-PE9-PadP$27)") (class "Default")
      (node (ref "U$1") (pin "P$27") (pinfunction "PE9_P$27") (pintype "bidirectional"))
    )
    (net (code "168") (name "unconnected-(U$1-PE10-PadP$28)") (class "Default")
      (node (ref "U$1") (pin "P$28") (pinfunction "PE10_P$28") (pintype "bidirectional"))
    )
    (net (code "169") (name "unconnected-(U$1-PE11-PadP$29)") (class "Default")
      (node (ref "U$1") (pin "P$29") (pinfunction "PE11_P$29") (pintype "bidirectional"))
    )
    (net (code "170") (name "unconnected-(U$1-PE12-PadP$30)") (class "Default")
      (node (ref "U$1") (pin "P$30") (pinfunction "PE12_P$30") (pintype "bidirectional"))
    )
    (net (code "171") (name "unconnected-(U$1-PE13-PadP$31)") (class "Default")
      (node (ref "U$1") (pin "P$31") (pinfunction "PE13_P$31") (pintype "bidirectional"))
    )
    (net (code "172") (name "unconnected-(U$1-PE14-PadP$32)") (class "Default")
      (node (ref "U$1") (pin "P$32") (pinfunction "PE14_P$32") (pintype "bidirectional"))
    )
    (net (code "173") (name "unconnected-(U$1-PE15-PadP$33)") (class "Default")
      (node (ref "U$1") (pin "P$33") (pinfunction "PE15_P$33") (pintype "bidirectional"))
    )
    (net (code "174") (name "unconnected-(U$1-PH0-PadP$57)") (class "Default")
      (node (ref "U$1") (pin "P$57") (pinfunction "PH0_P$57") (pintype "bidirectional"))
    )
    (net (code "175") (name "unconnected-(U$1-PH1-PadP$58)") (class "Default")
      (node (ref "U$1") (pin "P$58") (pinfunction "PH1_P$58") (pintype "bidirectional"))
    )
    (net (code "176") (name "unconnected-(U$1-VDD-PadP$3)") (class "Default")
      (node (ref "U$1") (pin "P$3") (pinfunction "VDD_P$3") (pintype "bidirectional"))
    )
    (net (code "177") (name "unconnected-(U$1-VDD1-PadP$4)") (class "Default")
      (node (ref "U$1") (pin "P$4") (pinfunction "VDD1_P$4") (pintype "bidirectional"))
    )
    (net (code "178") (name "unconnected-(U$1-VDD2-PadP$55)") (class "Default")
      (node (ref "U$1") (pin "P$55") (pinfunction "VDD2_P$55") (pintype "bidirectional"))
    )
    (net (code "179") (name "unconnected-(U$1-VDD3-PadP$56)") (class "Default")
      (node (ref "U$1") (pin "P$56") (pinfunction "VDD3_P$56") (pintype "bidirectional"))
    )
    (net (code "180") (name "unconnected-(U$1-VDD4-PadP$72)") (class "Default")
      (node (ref "U$1") (pin "P$72") (pinfunction "VDD4_P$72") (pintype "bidirectional"))
    )
  )
)
